# i2c-multiplexer-v2.net
KiCad netlist of a schematic drawn in EAGLE
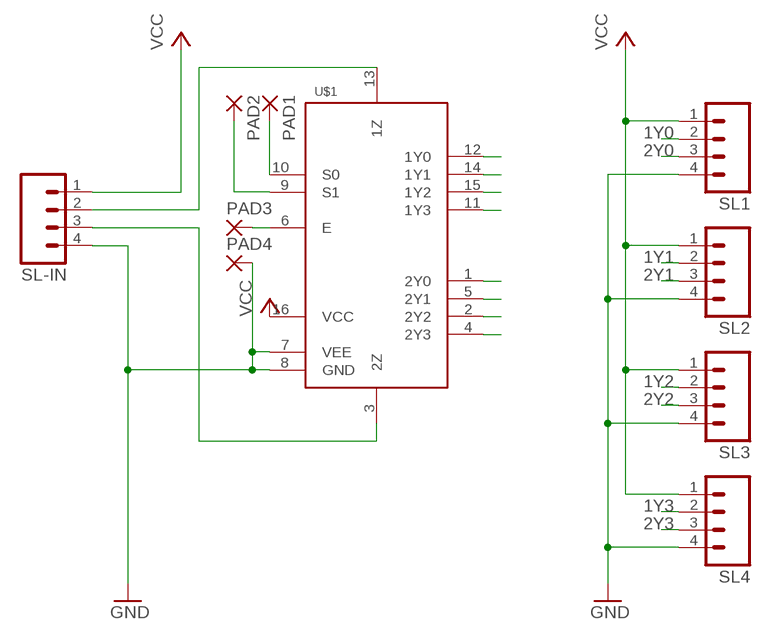
[diagram p0: schematic, sheet 1]

(export (version "E")
  (design (tool "Eeschema 10.0.6"))
  (components
    (comp (ref "PAD1")
      (value "1,6/0,8")
      (footprint "eagle-import:1,6_0,8")
      (libsource (lib "eagle-import") (part "1,6/0,8"))
    )
    (comp (ref "PAD2")
      (value "1,6/0,8")
      (footprint "eagle-import:1,6_0,8")
      (libsource (lib "eagle-import") (part "1,6/0,8"))
    )
    (comp (ref "PAD3")
      (value "1,6/0,8")
      (footprint "eagle-import:1,6_0,8")
      (libsource (lib "eagle-import") (part "1,6/0,8"))
    )
    (comp (ref "PAD4")
      (value "1,6/0,8")
      (footprint "eagle-import:1,6_0,8")
      (libsource (lib "eagle-import") (part "1,6/0,8"))
    )
    (comp (ref "SL-IN")
      (value "M04")
      (footprint "eagle-import:04P")
      (libsource (lib "eagle-import") (part "M04"))
    )
    (comp (ref "SL1")
      (value "M04")
      (footprint "eagle-import:04P")
      (libsource (lib "eagle-import") (part "M04"))
    )
    (comp (ref "SL2")
      (value "M04")
      (footprint "eagle-import:04P")
      (libsource (lib "eagle-import") (part "M04"))
    )
    (comp (ref "SL3")
      (value "M04")
      (footprint "eagle-import:04P")
      (libsource (lib "eagle-import") (part "M04"))
    )
    (comp (ref "SL4")
      (value "M04")
      (footprint "eagle-import:04P")
      (libsource (lib "eagle-import") (part "M04"))
    )
    (comp (ref "U$1")
      (value "74HC4052SO-16")
      (footprint "eagle-import:SO16")
      (libsource (lib "eagle-import") (part "74HC4052SO-16"))
    )
  )
  (nets
    (net (code "1") (name "/1Y0") (class "Default")
      (node (ref "SL1") (pin "2") (pinfunction "2_2") (pintype "passive"))
      (node (ref "U$1") (pin "12") (pinfunction "1Y0_12") (pintype "bidirectional"))
    )
    (net (code "2") (name "/1Y1") (class "Default")
      (node (ref "SL2") (pin "2") (pinfunction "2_2") (pintype "passive"))
      (node (ref "U$1") (pin "14") (pinfunction "1Y1_14") (pintype "bidirectional"))
    )
    (net (code "3") (name "/1Y2") (class "Default")
      (node (ref "SL3") (pin "2") (pinfunction "2_2") (pintype "passive"))
      (node (ref "U$1") (pin "15") (pinfunction "1Y2_15") (pintype "bidirectional"))
    )
    (net (code "4") (name "/1Y3") (class "Default")
      (node (ref "SL4") (pin "2") (pinfunction "2_2") (pintype "passive"))
      (node (ref "U$1") (pin "11") (pinfunction "1Y3_11") (pintype "bidirectional"))
    )
    (net (code "5") (name "/2Y0") (class "Default")
      (node (ref "SL1") (pin "3") (pinfunction "3_3") (pintype "passive"))
      (node (ref "U$1") (pin "1") (pinfunction "2Y0_1") (pintype "bidirectional"))
    )
    (net (code "6") (name "/2Y1") (class "Default")
      (node (ref "SL2") (pin "3") (pinfunction "3_3") (pintype "passive"))
      (node (ref "U$1") (pin "5") (pinfunction "2Y1_5") (pintype "bidirectional"))
    )
    (net (code "7") (name "/2Y2") (class "Default")
      (node (ref "SL3") (pin "3") (pinfunction "3_3") (pintype "passive"))
      (node (ref "U$1") (pin "2") (pinfunction "2Y2_2") (pintype "bidirectional"))
    )
    (net (code "8") (name "/2Y3") (class "Default")
      (node (ref "SL4") (pin "3") (pinfunction "3_3") (pintype "passive"))
      (node (ref "U$1") (pin "4") (pinfunction "2Y3_4") (pintype "bidirectional"))
    )
    (net (code "9") (name "GND") (class "Default")
      (node (ref "PAD4") (pin "1") (pinfunction "P_1") (pintype "passive"))
      (node (ref "SL-IN") (pin "4") (pinfunction "4_4") (pintype "passive"))
      (node (ref "SL1") (pin "4") (pinfunction "4_4") (pintype "passive"))
      (node (ref "SL2") (pin "4") (pinfunction "4_4") (pintype "passive"))
      (node (ref "SL3") (pin "4") (pinfunction "4_4") (pintype "passive"))
      (node (ref "SL4") (pin "4") (pinfunction "4_4") (pintype "passive"))
      (node (ref "U$1") (pin "7") (pinfunction "VEE_7") (pintype "power_in"))
      (node (ref "U$1") (pin "8") (pinfunction "GND_8") (pintype "power_in"))
    )
    (net (code "10") (name "Net-(PAD1-P)") (class "Default")
      (node (ref "PAD1") (pin "1") (pinfunction "P_1") (pintype "passive"))
      (node (ref "U$1") (pin "10") (pinfunction "S0_10") (pintype "bidirectional"))
    )
    (net (code "11") (name "Net-(PAD2-P)") (class "Default")
      (node (ref "PAD2") (pin "1") (pinfunction "P_1") (pintype "passive"))
      (node (ref "U$1") (pin "9") (pinfunction "S1_9") (pintype "bidirectional"))
    )
    (net (code "12") (name "Net-(PAD3-P)") (class "Default")
      (node (ref "PAD3") (pin "1") (pinfunction "P_1") (pintype "passive"))
      (node (ref "U$1") (pin "6") (pinfunction "E_6") (pintype "bidirectional"))
    )
    (net (code "13") (name "Net-(U$1-1Z)") (class "Default")
      (node (ref "SL-IN") (pin "2") (pinfunction "2_2") (pintype "passive"))
      (node (ref "U$1") (pin "13") (pinfunction "1Z_13") (pintype "input"))
    )
    (net (code "14") (name "Net-(U$1-2Z)") (class "Default")
      (node (ref "SL-IN") (pin "3") (pinfunction "3_3") (pintype "passive"))
      (node (ref "U$1") (pin "3") (pinfunction "2Z_3") (pintype "output"))
    )
    (net (code "15") (name "VCC") (class "Default")
      (node (ref "SL-IN") (pin "1") (pinfunction "1_1") (pintype "passive"))
      (node (ref "SL1") (pin "1") (pinfunction "1_1") (pintype "passive"))
      (node (ref "SL2") (pin "1") (pinfunction "1_1") (pintype "passive"))
      (node (ref "SL3") (pin "1") (pinfunction "1_1") (pintype "passive"))
      (node (ref "SL4") (pin "1") (pinfunction "1_1") (pintype "passive"))
      (node (ref "U$1") (pin "16") (pinfunction "VCC_16") (pintype "power_in"))
    )
  )
)
